# Rectifire_PFC_Solar.net
KiCad netlist of a schematic drawn in Altium Designer
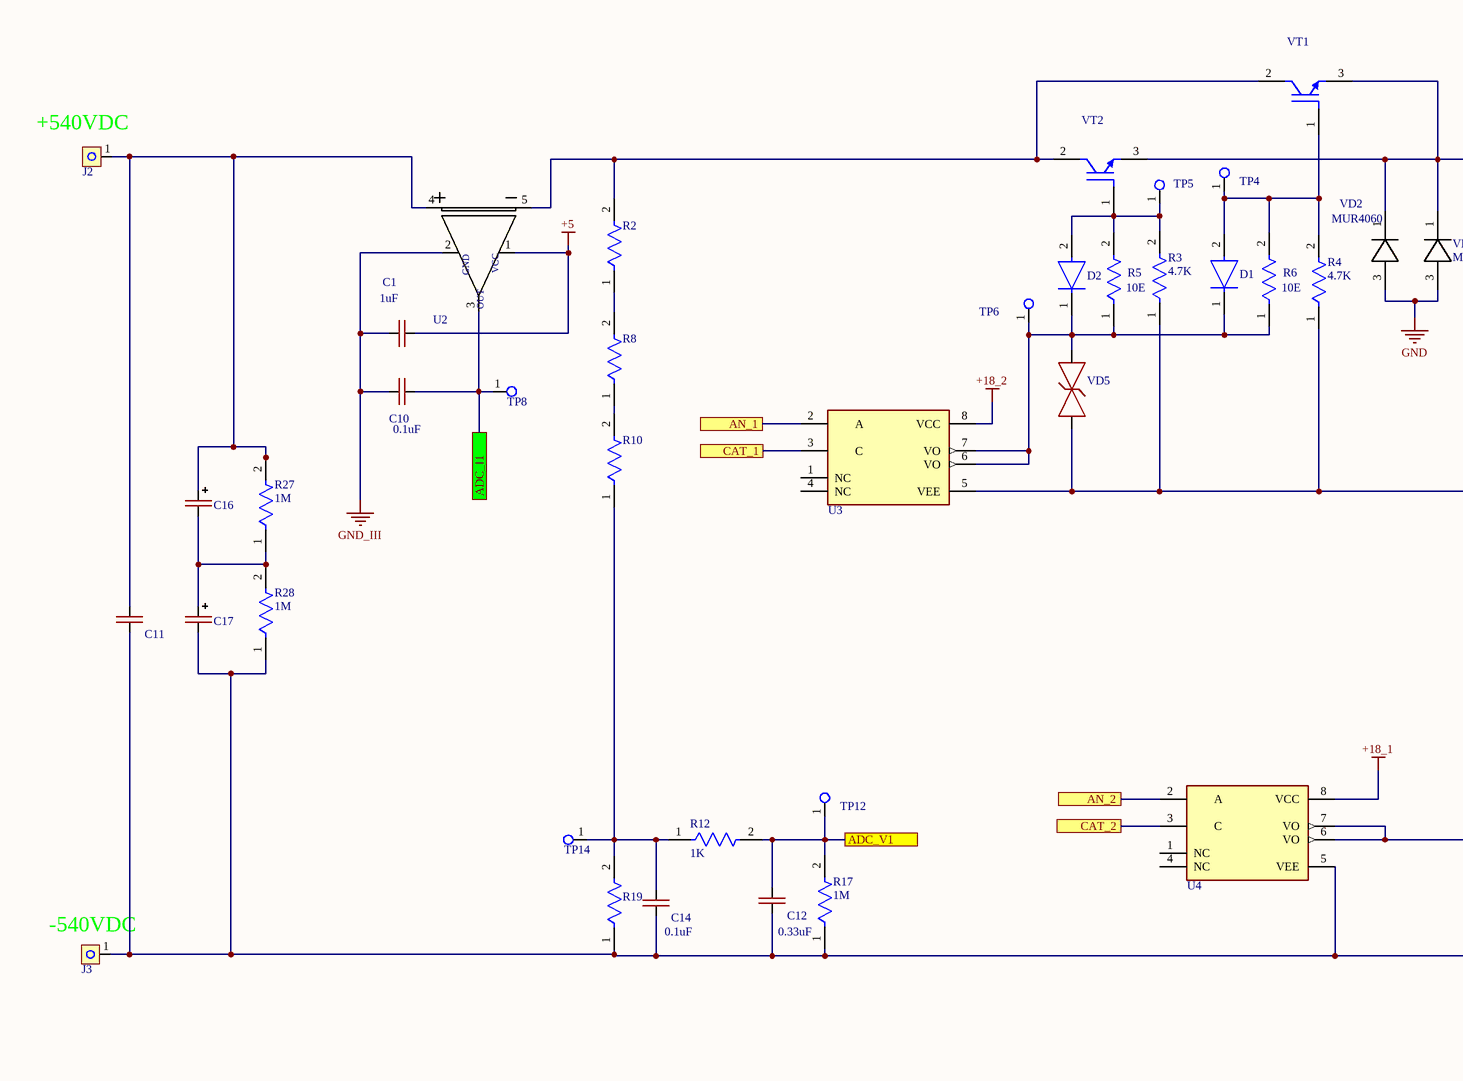
[diagram p0: Rectifire_PFC_Solar.SchDoc, top left]
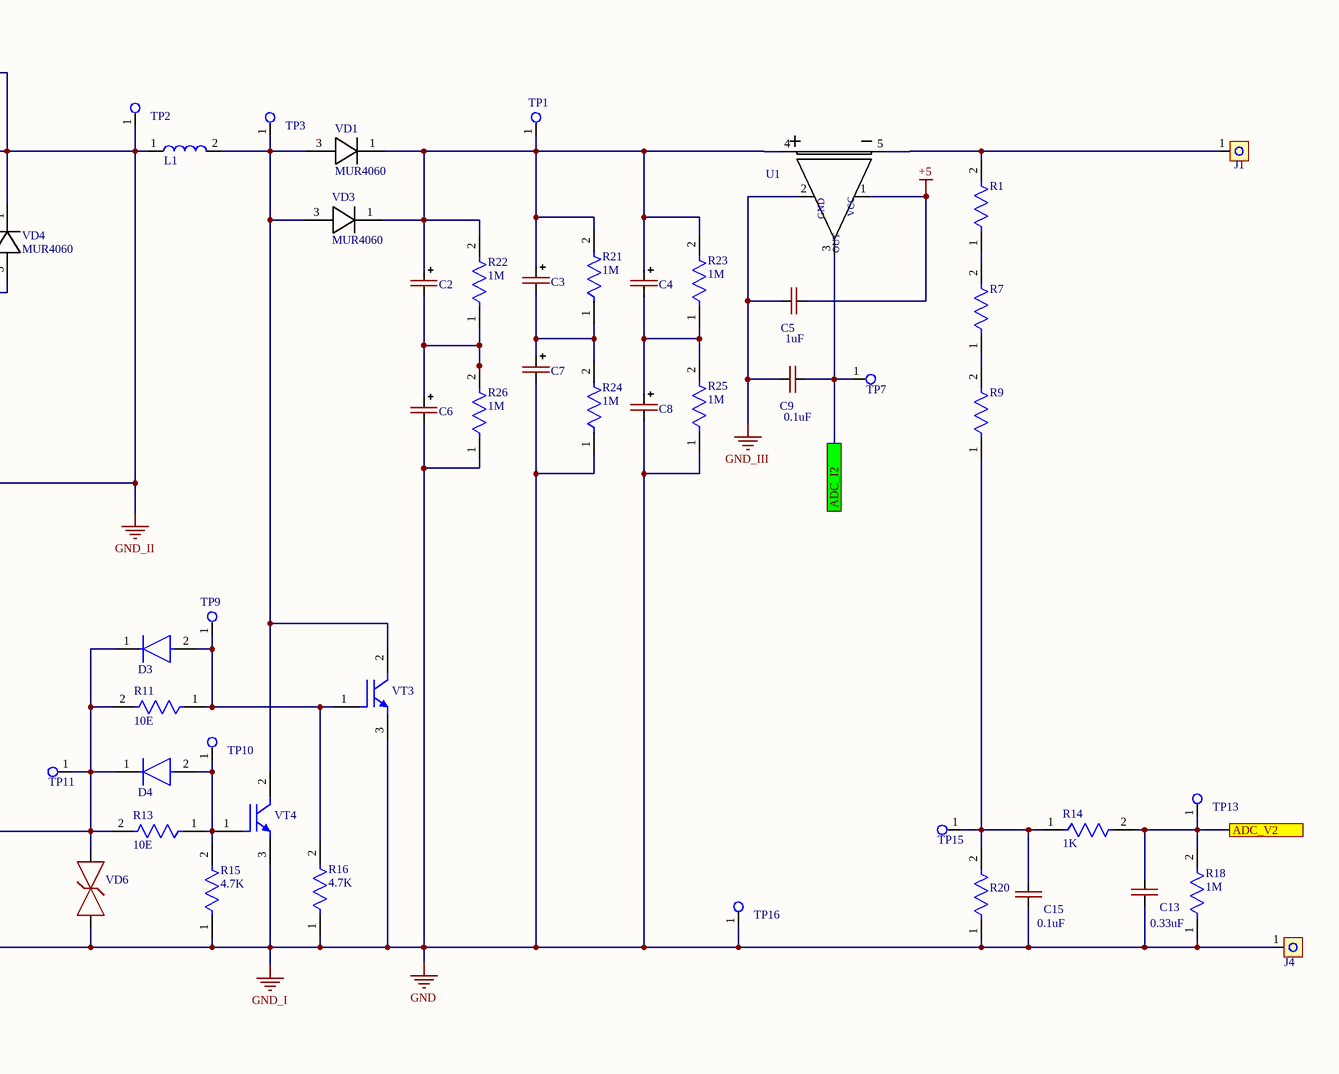
[diagram p1: Rectifire_PFC_Solar.SchDoc, top right]
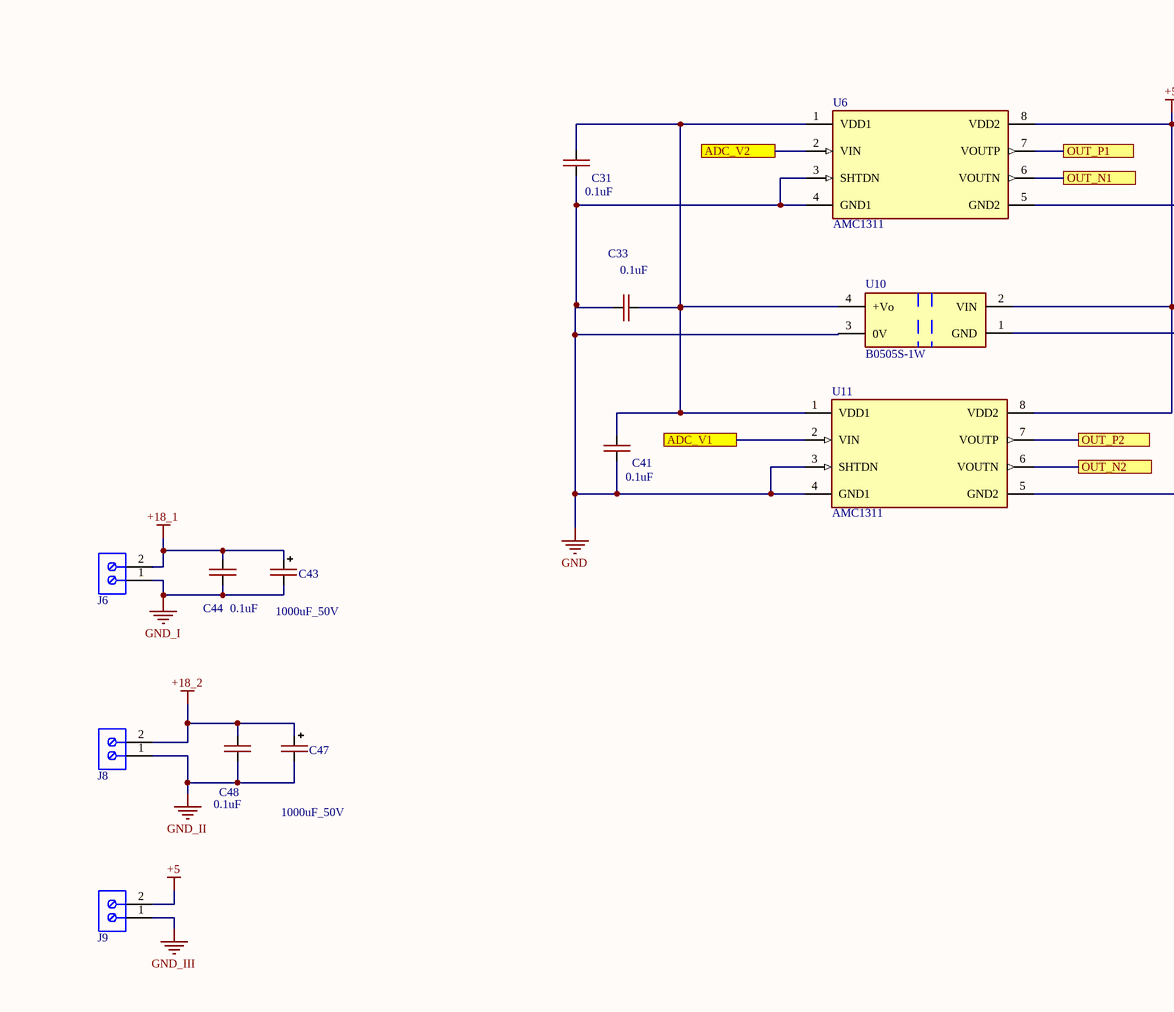
[diagram p2: Rectifire_PFC_Solar.SchDoc, bottom left]
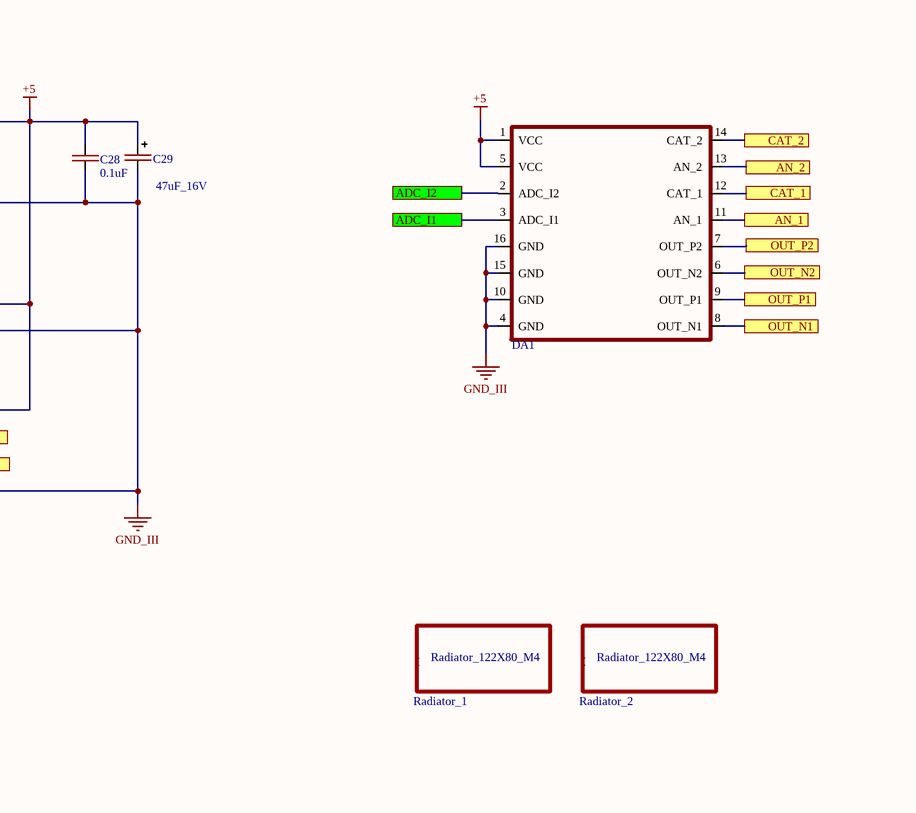
[diagram p3: Rectifire_PFC_Solar.SchDoc, bottom right]

(export (version "E")
  (design (tool "Eeschema 10.0.6"))
  (components
    (comp (ref "C1")
      (value "1uF")
      (footprint "CAP-0805")
      (libsource (lib "PASSIVE_COMPONENTS") (part "CAP-NON-POLAR"))
    )
    (comp (ref "C2")
      (value "CAP-POLAR")
      (footprint "CAP 100uF_500V 22x40mm")
      (libsource (lib "PASSIVE_COMPONENTS") (part "CAP-POLAR"))
    )
    (comp (ref "C3")
      (value "CAP-POLAR")
      (footprint "CAP 100uF_500V 22x40mm")
      (libsource (lib "PASSIVE_COMPONENTS") (part "CAP-POLAR"))
    )
    (comp (ref "C4")
      (value "CAP-POLAR")
      (footprint "CAP 100uF_500V 22x40mm")
      (libsource (lib "PASSIVE_COMPONENTS") (part "CAP-POLAR"))
    )
    (comp (ref "C5")
      (value "1uF")
      (footprint "CAP-0805")
      (libsource (lib "PASSIVE_COMPONENTS") (part "CAP-NON-POLAR"))
    )
    (comp (ref "C6")
      (value "CAP-POLAR")
      (footprint "CAP 100uF_500V 22x40mm")
      (libsource (lib "PASSIVE_COMPONENTS") (part "CAP-POLAR"))
    )
    (comp (ref "C7")
      (value "CAP-POLAR")
      (footprint "CAP 100uF_500V 22x40mm")
      (libsource (lib "PASSIVE_COMPONENTS") (part "CAP-POLAR"))
    )
    (comp (ref "C8")
      (value "CAP-POLAR")
      (footprint "CAP 100uF_500V 22x40mm")
      (libsource (lib "PASSIVE_COMPONENTS") (part "CAP-POLAR"))
    )
    (comp (ref "C9")
      (value "0.1uF")
      (footprint "CAP-0805")
      (libsource (lib "PASSIVE_COMPONENTS") (part "CAP-NON-POLAR"))
    )
    (comp (ref "C10")
      (value "0.1uF")
      (footprint "CAP-0805")
      (libsource (lib "PASSIVE_COMPONENTS") (part "CAP-NON-POLAR"))
    )
    (comp (ref "C11")
      (value "CAP-NON-POLAR")
      (footprint "CAP_4.7uF_630V")
      (libsource (lib "PASSIVE_COMPONENTS") (part "CAP-NON-POLAR"))
    )
    (comp (ref "C12")
      (value "0.33uF")
      (footprint "CAP-0805")
      (libsource (lib "PASSIVE_COMPONENTS") (part "CAP-NON-POLAR"))
    )
    (comp (ref "C13")
      (value "0.33uF")
      (footprint "CAP-0805")
      (libsource (lib "PASSIVE_COMPONENTS") (part "CAP-NON-POLAR"))
    )
    (comp (ref "C14")
      (value "0.1uF")
      (footprint "CAP-0805")
      (libsource (lib "PASSIVE_COMPONENTS") (part "CAP-NON-POLAR"))
    )
    (comp (ref "C15")
      (value "0.1uF")
      (footprint "CAP-0805")
      (libsource (lib "PASSIVE_COMPONENTS") (part "CAP-NON-POLAR"))
    )
    (comp (ref "C16")
      (value "CAP-POLAR")
      (footprint "CAP_POL_36X60")
      (libsource (lib "PASSIVE_COMPONENTS") (part "CAP-POLAR"))
    )
    (comp (ref "C17")
      (value "CAP-POLAR")
      (footprint "CAP_POL_36X60")
      (libsource (lib "PASSIVE_COMPONENTS") (part "CAP-POLAR"))
    )
    (comp (ref "C28")
      (value "0.1uF")
      (footprint "CAP-0805")
      (libsource (lib "PASSIVE_COMPONENTS") (part "CAP-NON-POLAR"))
    )
    (comp (ref "C29")
      (value "47uF_16V")
      (footprint "CAP-TAN-D")
      (libsource (lib "PASSIVE_COMPONENTS") (part "CAP-POLAR"))
    )
    (comp (ref "C31")
      (value "0.1uF")
      (footprint "CAP-0805")
      (libsource (lib "PASSIVE_COMPONENTS") (part "CAP-NON-POLAR"))
    )
    (comp (ref "C33")
      (value "0.1uF")
      (footprint "CAP-0805")
      (libsource (lib "PASSIVE_COMPONENTS") (part "CAP-NON-POLAR"))
    )
    (comp (ref "C41")
      (value "0.1uF")
      (footprint "CAP-0805")
      (libsource (lib "PASSIVE_COMPONENTS") (part "CAP-NON-POLAR"))
    )
    (comp (ref "C43")
      (value "1000uF_50V")
      (footprint "CAPPOL-16x25")
      (libsource (lib "PASSIVE_COMPONENTS") (part "CAP-POLAR"))
    )
    (comp (ref "C44")
      (value "0.1uF")
      (footprint "CAP-0805")
      (libsource (lib "PASSIVE_COMPONENTS") (part "CAP-NON-POLAR"))
    )
    (comp (ref "C47")
      (value "1000uF_50V")
      (footprint "CAPPOL-16x25")
      (libsource (lib "PASSIVE_COMPONENTS") (part "CAP-POLAR"))
    )
    (comp (ref "C48")
      (value "0.1uF")
      (footprint "CAP-0805")
      (libsource (lib "PASSIVE_COMPONENTS") (part "CAP-NON-POLAR"))
    )
    (comp (ref "D1") (value "US1G") (footprint "DO-214AA") (libsource (lib "Diodes") (part "US1G")))
    (comp (ref "D2") (value "US1G") (footprint "DO-214AA") (libsource (lib "Diodes") (part "US1G")))
    (comp (ref "D3") (value "US1G") (footprint "DO-214AA") (libsource (lib "Diodes") (part "US1G")))
    (comp (ref "D4") (value "US1G") (footprint "DO-214AA") (libsource (lib "Diodes") (part "US1G")))
    (comp (ref "DA1")
      (value "BOARD_PFC")
      (footprint "BOARD_PFC")
      (libsource (lib "BOARD_PFC") (part "BOARD_PFC"))
    )
    (comp (ref "J1")
      (value "MG_136_HT")
      (footprint "Conn_MEIGAN_MG136HT")
      (libsource (lib "") (part "Connector_MEIGAN_MG136HT_1"))
    )
    (comp (ref "J2")
      (value "MG_136_HT")
      (footprint "Conn_MEIGAN_MG136HT")
      (libsource (lib "Connectors") (part "Connector_MEIGAN_MG136HT"))
    )
    (comp (ref "J3")
      (value "MG_136_HT")
      (footprint "Conn_MEIGAN_MG136HT")
      (libsource (lib "Connectors") (part "Connector_MEIGAN_MG136HT"))
    )
    (comp (ref "J4")
      (value "MG_136_HT")
      (footprint "Conn_MEIGAN_MG136HT")
      (libsource (lib "") (part "Connector_MEIGAN_MG136HT_1"))
    )
    (comp (ref "J6")
      (value "691102710002")
      (footprint "691102710002")
      (description "WR-TBL Series 102 Horizontal Entry Modular, THT, pitch 5mm, 2p")
      (fields (field (name "MANUFACTURER") "Wurth Elektronik"))
      (libsource (lib "Altium_WR-TBL (rev23f)") (part "691102710002"))
    )
    (comp (ref "J8")
      (value "691102710002")
      (footprint "691102710002")
      (description "WR-TBL Series 102 Horizontal Entry Modular, THT, pitch 5mm, 2p")
      (fields (field (name "MANUFACTURER") "Wurth Elektronik"))
      (libsource (lib "Altium_WR-TBL (rev23f)") (part "691102710002"))
    )
    (comp (ref "J9")
      (value "691102710002")
      (footprint "691102710002")
      (description "WR-TBL Series 102 Horizontal Entry Modular, THT, pitch 5mm, 2p")
      (fields (field (name "MANUFACTURER") "Wurth Elektronik"))
      (libsource (lib "Altium_WR-TBL (rev23f)") (part "691102710002"))
    )
    (comp (ref "L1") (value "Coil") (footprint "30A_10uH") (libsource (lib "Transformers") (part "Coil")))
    (comp (ref "R1")
      (value "~")
      (footprint "RES-2512")
      (libsource (lib "PASSIVE_COMPONENTS") (part "RES-CONST"))
    )
    (comp (ref "R2")
      (value "~")
      (footprint "RES-2512")
      (libsource (lib "PASSIVE_COMPONENTS") (part "RES-CONST"))
    )
    (comp (ref "R3")
      (value "4.7K")
      (footprint "RES-0805")
      (libsource (lib "PASSIVE_COMPONENTS") (part "RES-CONST"))
    )
    (comp (ref "R4")
      (value "4.7K")
      (footprint "RES-0805")
      (libsource (lib "PASSIVE_COMPONENTS") (part "RES-CONST"))
    )
    (comp (ref "R5")
      (value "10E")
      (footprint "RES_SMD_1210_IPC_A")
      (libsource (lib "PASSIVE_COMPONENTS") (part "RES_1210"))
    )
    (comp (ref "R6")
      (value "10E")
      (footprint "RES_SMD_1210_IPC_A")
      (libsource (lib "PASSIVE_COMPONENTS") (part "RES_1210"))
    )
    (comp (ref "R7")
      (value "~")
      (footprint "RES-2512")
      (libsource (lib "PASSIVE_COMPONENTS") (part "RES-CONST"))
    )
    (comp (ref "R8")
      (value "~")
      (footprint "RES-2512")
      (libsource (lib "PASSIVE_COMPONENTS") (part "RES-CONST"))
    )
    (comp (ref "R9")
      (value "~")
      (footprint "RES-2512")
      (libsource (lib "PASSIVE_COMPONENTS") (part "RES-CONST"))
    )
    (comp (ref "R10")
      (value "~")
      (footprint "RES-2512")
      (libsource (lib "PASSIVE_COMPONENTS") (part "RES-CONST"))
    )
    (comp (ref "R11")
      (value "10E")
      (footprint "RES_SMD_1210_IPC_A")
      (libsource (lib "PASSIVE_COMPONENTS") (part "RES_1210"))
    )
    (comp (ref "R12")
      (value "1K")
      (footprint "RES-0805")
      (libsource (lib "PASSIVE_COMPONENTS") (part "RES-CONST"))
    )
    (comp (ref "R13")
      (value "10E")
      (footprint "RES_SMD_1210_IPC_A")
      (libsource (lib "PASSIVE_COMPONENTS") (part "RES_1210"))
    )
    (comp (ref "R14")
      (value "1K")
      (footprint "RES-0805")
      (libsource (lib "PASSIVE_COMPONENTS") (part "RES-CONST"))
    )
    (comp (ref "R15")
      (value "4.7K")
      (footprint "RES-0805")
      (libsource (lib "PASSIVE_COMPONENTS") (part "RES-CONST"))
    )
    (comp (ref "R16")
      (value "4.7K")
      (footprint "RES-0805")
      (libsource (lib "PASSIVE_COMPONENTS") (part "RES-CONST"))
    )
    (comp (ref "R17")
      (value "1M")
      (footprint "RES-0805")
      (libsource (lib "PASSIVE_COMPONENTS") (part "RES-CONST"))
    )
    (comp (ref "R18")
      (value "1M")
      (footprint "RES-0805")
      (libsource (lib "PASSIVE_COMPONENTS") (part "RES-CONST"))
    )
    (comp (ref "R19")
      (value "RES_1210")
      (footprint "RES_SMD_1210_IPC_B")
      (libsource (lib "PASSIVE_COMPONENTS") (part "RES_1210"))
    )
    (comp (ref "R20")
      (value "RES_1210")
      (footprint "RES_SMD_1210_IPC_B")
      (libsource (lib "PASSIVE_COMPONENTS") (part "RES_1210"))
    )
    (comp (ref "R21")
      (value "1M")
      (footprint "RES-2512")
      (description "4.7K")
      (libsource (lib "PASSIVE_COMPONENTS") (part "RES-CONST"))
    )
    (comp (ref "R22")
      (value "1M")
      (footprint "RES-2512")
      (description "4.7K")
      (libsource (lib "PASSIVE_COMPONENTS") (part "RES-CONST"))
    )
    (comp (ref "R23")
      (value "1M")
      (footprint "RES-2512")
      (description "4.7K")
      (libsource (lib "PASSIVE_COMPONENTS") (part "RES-CONST"))
    )
    (comp (ref "R24")
      (value "1M")
      (footprint "RES-2512")
      (description "4.7K")
      (libsource (lib "PASSIVE_COMPONENTS") (part "RES-CONST"))
    )
    (comp (ref "R25")
      (value "1M")
      (footprint "RES-2512")
      (description "4.7K")
      (libsource (lib "PASSIVE_COMPONENTS") (part "RES-CONST"))
    )
    (comp (ref "R26")
      (value "1M")
      (footprint "RES-2512")
      (description "4.7K")
      (libsource (lib "PASSIVE_COMPONENTS") (part "RES-CONST"))
    )
    (comp (ref "R27")
      (value "1M")
      (footprint "RES-2512")
      (description "4.7K")
      (libsource (lib "PASSIVE_COMPONENTS") (part "RES-CONST"))
    )
    (comp (ref "R28")
      (value "1M")
      (footprint "RES-2512")
      (description "4.7K")
      (libsource (lib "PASSIVE_COMPONENTS") (part "RES-CONST"))
    )
    (comp (ref "Radiator_1")
      (value "Radiator_122X80_M4")
      (footprint "Radiator_122X80_M4")
      (libsource (lib "Radiator_122X80_M4") (part "Radiator_122X80_M4"))
    )
    (comp (ref "Radiator_2")
      (value "Radiator_122X80_M4")
      (footprint "Radiator_122X80_M4")
      (libsource (lib "Radiator_122X80_M4") (part "Radiator_122X80_M4"))
    )
    (comp (ref "TP1")
      (value "Test_Point_PCB")
      (footprint "Test_Point")
      (description "Test_Point")
      (libsource (lib "Connectors") (part "TP_PCB?"))
    )
    (comp (ref "TP2")
      (value "Test_Point_PCB")
      (footprint "Test_Point")
      (description "Test_Point")
      (libsource (lib "Connectors") (part "TP_PCB?"))
    )
    (comp (ref "TP3")
      (value "Test_Point_PCB")
      (footprint "Test_Point")
      (description "Test_Point")
      (libsource (lib "Connectors") (part "TP_PCB?"))
    )
    (comp (ref "TP4")
      (value "Test_Point_PCB")
      (footprint "Test_Point")
      (description "Test_Point")
      (libsource (lib "Connectors") (part "TP_PCB?"))
    )
    (comp (ref "TP5")
      (value "Test_Point_PCB")
      (footprint "Test_Point")
      (description "Test_Point")
      (libsource (lib "Connectors") (part "TP_PCB?"))
    )
    (comp (ref "TP6")
      (value "Test_Point_PCB")
      (footprint "Test_Point")
      (description "Test_Point")
      (libsource (lib "Connectors") (part "TP_PCB?"))
    )
    (comp (ref "TP7")
      (value "Test_Point_PCB")
      (footprint "Test_Point")
      (description "Test_Point")
      (libsource (lib "Connectors") (part "TP_PCB?"))
    )
    (comp (ref "TP8")
      (value "Test_Point_PCB")
      (footprint "Test_Point")
      (description "Test_Point")
      (libsource (lib "Connectors") (part "TP_PCB?"))
    )
    (comp (ref "TP9")
      (value "Test_Point_PCB")
      (footprint "Test_Point")
      (description "Test_Point")
      (libsource (lib "Connectors") (part "TP_PCB?"))
    )
    (comp (ref "TP10")
      (value "Test_Point_PCB")
      (footprint "Test_Point")
      (description "Test_Point")
      (libsource (lib "Connectors") (part "TP_PCB?"))
    )
    (comp (ref "TP11")
      (value "Test_Point_PCB")
      (footprint "Test_Point")
      (description "Test_Point")
      (libsource (lib "Connectors") (part "TP_PCB?"))
    )
    (comp (ref "TP12")
      (value "Test_Point_PCB")
      (footprint "Test_Point")
      (description "Test_Point")
      (libsource (lib "Connectors") (part "TP_PCB?"))
    )
    (comp (ref "TP13")
      (value "Test_Point_PCB")
      (footprint "Test_Point")
      (description "Test_Point")
      (libsource (lib "Connectors") (part "TP_PCB?"))
    )
    (comp (ref "TP14")
      (value "Test_Point_PCB")
      (footprint "Test_Point")
      (description "Test_Point")
      (libsource (lib "Connectors") (part "TP_PCB?"))
    )
    (comp (ref "TP15")
      (value "Test_Point_PCB")
      (footprint "Test_Point")
      (description "Test_Point")
      (libsource (lib "Connectors") (part "TP_PCB?"))
    )
    (comp (ref "TP16")
      (value "Test_Point_PCB")
      (footprint "Test_Point")
      (description "Test_Point")
      (libsource (lib "Connectors") (part "TP_PCB?"))
    )
    (comp (ref "U1")
      (value "ACS758")
      (footprint "ACS758-100")
      (libsource (lib "Integrated_Circuts") (part "ACS758"))
    )
    (comp (ref "U2")
      (value "ACS758")
      (footprint "ACS758-100")
      (libsource (lib "Integrated_Circuts") (part "ACS758"))
    )
    (comp (ref "U3")
      (value "HCPL-3120")
      (footprint "HCPL-3120")
      (libsource (lib "Integrated_Circuts") (part "HCPL-3120"))
    )
    (comp (ref "U4")
      (value "HCPL-3120")
      (footprint "HCPL-3120")
      (libsource (lib "Integrated_Circuts") (part "HCPL-3120"))
    )
    (comp (ref "U6")
      (value "AMC1311")
      (footprint "FP-DWV0008A-MFG")
      (libsource (lib "Integrated_Circuts") (part "AMC1311"))
    )
    (comp (ref "U10")
      (value "B0505S-1W")
      (footprint "B0505S-1W")
      (libsource (lib "Integrated_Circuts") (part "B0505S-1W"))
    )
    (comp (ref "U11")
      (value "AMC1311")
      (footprint "FP-DWV0008A-MFG")
      (libsource (lib "Integrated_Circuts") (part "AMC1311"))
    )
    (comp (ref "VD1") (value "MUR4060") (footprint "TO-247-2") (libsource (lib "Diodes") (part "MUR4060")))
    (comp (ref "VD2") (value "MUR4060") (footprint "TO-247-2") (libsource (lib "Diodes") (part "MUR4060")))
    (comp (ref "VD3") (value "MUR4060") (footprint "TO-247-2") (libsource (lib "Diodes") (part "MUR4060")))
    (comp (ref "VD4") (value "MUR4060") (footprint "TO-247-2") (libsource (lib "Diodes") (part "MUR4060")))
    (comp (ref "VD5")
      (value "Suppressor")
      (footprint "DO-214AA")
      (libsource (lib "Diodes") (part "Suppressor"))
    )
    (comp (ref "VD6")
      (value "Suppressor")
      (footprint "DO-214AA")
      (libsource (lib "Diodes") (part "Suppressor"))
    )
    (comp (ref "VT1")
      (value "IGBT 60N120T")
      (footprint "TO-264-3")
      (description "IGBT 60N120T TO-264-3")
      (libsource (lib "Transistors") (part "IGBT 60N120T"))
    )
    (comp (ref "VT2")
      (value "IGBT 60N120T")
      (footprint "TO-264-3")
      (description "IGBT 60N120T TO-264-3")
      (libsource (lib "Transistors") (part "IGBT 60N120T"))
    )
    (comp (ref "VT3")
      (value "IGBT 60N120T")
      (footprint "TO-264-3")
      (description "IGBT 60N120T TO-264-3")
      (libsource (lib "Transistors") (part "IGBT 60N120T"))
    )
    (comp (ref "VT4")
      (value "IGBT 60N120T")
      (footprint "TO-264-3")
      (description "IGBT 60N120T TO-264-3")
      (libsource (lib "Transistors") (part "IGBT 60N120T"))
    )
  )
  (nets
    (net (code "1") (name "+5") (class "Default")
      (node (ref "C1") (pin "2") (pinfunction "2_2") (pintype "passive"))
      (node (ref "C28") (pin "1") (pinfunction "1_1") (pintype "passive"))
      (node (ref "C29") (pin "1") (pinfunction "+_1") (pintype "passive"))
      (node (ref "C5") (pin "2") (pinfunction "2_2") (pintype "passive"))
      (node (ref "DA1") (pin "1") (pinfunction "VCC_1") (pintype "passive"))
      (node (ref "DA1") (pin "5") (pinfunction "VCC_5") (pintype "passive"))
      (node (ref "J9") (pin "2") (pinfunction "2_2") (pintype "passive"))
      (node (ref "U1") (pin "1") (pinfunction "+VCC_1") (pintype "passive"))
      (node (ref "U10") (pin "2") (pinfunction "VIN_2") (pintype "power_in"))
      (node (ref "U11") (pin "8") (pinfunction "VDD2_8") (pintype "power_in"))
      (node (ref "U2") (pin "1") (pinfunction "+VCC_1") (pintype "passive"))
      (node (ref "U6") (pin "8") (pinfunction "VDD2_8") (pintype "power_in"))
    )
    (net (code "2") (name "+18_1") (class "Default")
      (node (ref "C43") (pin "1") (pinfunction "+_1") (pintype "passive"))
      (node (ref "C44") (pin "2") (pinfunction "2_2") (pintype "passive"))
      (node (ref "J6") (pin "2") (pinfunction "2_2") (pintype "passive"))
      (node (ref "U4") (pin "8") (pinfunction "VCC_8") (pintype "power_in"))
    )
    (net (code "3") (name "+18_2") (class "Default")
      (node (ref "C47") (pin "1") (pinfunction "+_1") (pintype "passive"))
      (node (ref "C48") (pin "2") (pinfunction "2_2") (pintype "passive"))
      (node (ref "J8") (pin "2") (pinfunction "2_2") (pintype "passive"))
      (node (ref "U3") (pin "8") (pinfunction "VCC_8") (pintype "power_in"))
    )
    (net (code "4") (name "/ADC_I1") (class "Default")
      (node (ref "C10") (pin "2") (pinfunction "2_2") (pintype "passive"))
      (node (ref "DA1") (pin "3") (pinfunction "ADC_I1_3") (pintype "passive"))
      (node (ref "TP8") (pin "1") (pinfunction "G9_1") (pintype "passive"))
      (node (ref "U2") (pin "3") (pinfunction "OUT_3") (pintype "passive"))
    )
    (net (code "5") (name "/ADC_I2") (class "Default")
      (node (ref "C9") (pin "2") (pinfunction "2_2") (pintype "passive"))
      (node (ref "DA1") (pin "2") (pinfunction "ADC_I2_2") (pintype "passive"))
      (node (ref "TP7") (pin "1") (pinfunction "G9_1") (pintype "passive"))
      (node (ref "U1") (pin "3") (pinfunction "OUT_3") (pintype "passive"))
    )
    (net (code "6") (name "/ADC_V1") (class "Default")
      (node (ref "C12") (pin "2") (pinfunction "2_2") (pintype "passive"))
      (node (ref "R12") (pin "2") (pinfunction "2_2") (pintype "passive"))
      (node (ref "R17") (pin "2") (pinfunction "2_2") (pintype "passive"))
      (node (ref "TP12") (pin "1") (pinfunction "G9_1") (pintype "passive"))
      (node (ref "U11") (pin "2") (pinfunction "VIN_2") (pintype "input"))
    )
    (net (code "7") (name "/ADC_V2") (class "Default")
      (node (ref "C13") (pin "2") (pinfunction "2_2") (pintype "passive"))
      (node (ref "R14") (pin "2") (pinfunction "2_2") (pintype "passive"))
      (node (ref "R18") (pin "2") (pinfunction "2_2") (pintype "passive"))
      (node (ref "TP13") (pin "1") (pinfunction "G9_1") (pintype "passive"))
      (node (ref "U6") (pin "2") (pinfunction "VIN_2") (pintype "input"))
    )
    (net (code "8") (name "/AN_1") (class "Default")
      (node (ref "DA1") (pin "11") (pinfunction "AN_1_11") (pintype "passive"))
      (node (ref "U3") (pin "2") (pinfunction "A_2") (pintype "passive"))
    )
    (net (code "9") (name "/AN_2") (class "Default")
      (node (ref "DA1") (pin "13") (pinfunction "AN_2_13") (pintype "passive"))
      (node (ref "U4") (pin "2") (pinfunction "A_2") (pintype "passive"))
    )
    (net (code "10") (name "/CAT_1") (class "Default")
      (node (ref "DA1") (pin "12") (pinfunction "CAT_1_12") (pintype "passive"))
      (node (ref "U3") (pin "3") (pinfunction "C_3") (pintype "passive"))
    )
    (net (code "11") (name "/CAT_2") (class "Default")
      (node (ref "DA1") (pin "14") (pinfunction "CAT_2_14") (pintype "passive"))
      (node (ref "U4") (pin "3") (pinfunction "C_3") (pintype "passive"))
    )
    (net (code "12") (name "/OUT_N1") (class "Default")
      (node (ref "DA1") (pin "8") (pinfunction "OUT_N1_8") (pintype "passive"))
      (node (ref "U6") (pin "6") (pinfunction "VOUTN_6") (pintype "output"))
    )
    (net (code "13") (name "/OUT_N2") (class "Default")
      (node (ref "DA1") (pin "6") (pinfunction "OUT_N2_6") (pintype "passive"))
      (node (ref "U11") (pin "6") (pinfunction "VOUTN_6") (pintype "output"))
    )
    (net (code "14") (name "/OUT_P1") (class "Default")
      (node (ref "DA1") (pin "9") (pinfunction "OUT_P1_9") (pintype "passive"))
      (node (ref "U6") (pin "7") (pinfunction "VOUTP_7") (pintype "output"))
    )
    (net (code "15") (name "/OUT_P2") (class "Default")
      (node (ref "DA1") (pin "7") (pinfunction "OUT_P2_7") (pintype "passive"))
      (node (ref "U11") (pin "7") (pinfunction "VOUTP_7") (pintype "output"))
    )
    (net (code "16") (name "GND") (class "Default")
      (node (ref "C11") (pin "1") (pinfunction "1_1") (pintype "passive"))
      (node (ref "C12") (pin "1") (pinfunction "1_1") (pintype "passive"))
      (node (ref "C13") (pin "1") (pinfunction "1_1") (pintype "passive"))
      (node (ref "C14") (pin "1") (pinfunction "1_1") (pintype "passive"))
      (node (ref "C15") (pin "1") (pinfunction "1_1") (pintype "passive"))
      (node (ref "C17") (pin "2") (pinfunction "-_2") (pintype "passive"))
      (node (ref "C31") (pin "1") (pinfunction "1_1") (pintype "passive"))
      (node (ref "C33") (pin "2") (pinfunction "2_2") (pintype "passive"))
      (node (ref "C41") (pin "1") (pinfunction "1_1") (pintype "passive"))
      (node (ref "C43") (pin "2") (pinfunction "-_2") (pintype "passive"))
      (node (ref "C44") (pin "1") (pinfunction "1_1") (pintype "passive"))
      (node (ref "C6") (pin "2") (pinfunction "-_2") (pintype "passive"))
      (node (ref "C7") (pin "2") (pinfunction "-_2") (pintype "passive"))
      (node (ref "C8") (pin "2") (pinfunction "-_2") (pintype "passive"))
      (node (ref "J3") (pin "1") (pinfunction "17_1") (pintype "passive"))
      (node (ref "J4") (pin "1") (pinfunction "17_1") (pintype "passive"))
      (node (ref "J6") (pin "1") (pinfunction "1_1") (pintype "passive"))
      (node (ref "R15") (pin "1") (pinfunction "1_1") (pintype "passive"))
      (node (ref "R16") (pin "1") (pinfunction "1_1") (pintype "passive"))
      (node (ref "R17") (pin "1") (pinfunction "1_1") (pintype "passive"))
      (node (ref "R18") (pin "1") (pinfunction "1_1") (pintype "passive"))
      (node (ref "R19") (pin "1") (pinfunction "1_1") (pintype "passive"))
      (node (ref "R20") (pin "1") (pinfunction "1_1") (pintype "passive"))
      (node (ref "R24") (pin "1") (pinfunction "1_1") (pintype "passive"))
      (node (ref "R25") (pin "1") (pinfunction "1_1") (pintype "passive"))
      (node (ref "R26") (pin "1") (pinfunction "1_1") (pintype "passive"))
      (node (ref "R28") (pin "1") (pinfunction "1_1") (pintype "passive"))
      (node (ref "TP16") (pin "1") (pinfunction "G9_1") (pintype "passive"))
      (node (ref "U10") (pin "3") (pinfunction "0V_3") (pintype "power_in"))
      (node (ref "U11") (pin "3") (pinfunction "SHTDN_3") (pintype "input"))
      (node (ref "U11") (pin "4") (pinfunction "GND1_4") (pintype "power_in"))
      (node (ref "U4") (pin "5") (pinfunction "VEE_5") (pintype "power_in"))
      (node (ref "U6") (pin "3") (pinfunction "SHTDN_3") (pintype "input"))
      (node (ref "U6") (pin "4") (pinfunction "GND1_4") (pintype "power_in"))
      (node (ref "VD2") (pin "3") (pinfunction "3_3") (pintype "passive"))
      (node (ref "VD4") (pin "3") (pinfunction "3_3") (pintype "passive"))
      (node (ref "VD6") (pin "1") (pinfunction "C_1") (pintype "passive"))
      (node (ref "VT3") (pin "3") (pinfunction "E_3") (pintype "passive"))
      (node (ref "VT4") (pin "3") (pinfunction "E_3") (pintype "passive"))
    )
    (net (code "17") (name "GND_II") (class "Default")
      (node (ref "C47") (pin "2") (pinfunction "-_2") (pintype "passive"))
      (node (ref "C48") (pin "1") (pinfunction "1_1") (pintype "passive"))
      (node (ref "J8") (pin "1") (pinfunction "1_1") (pintype "passive"))
      (node (ref "L1") (pin "1") (pinfunction "1_1") (pintype "passive"))
      (node (ref "R3") (pin "1") (pinfunction "1_1") (pintype "passive"))
      (node (ref "R4") (pin "1") (pinfunction "1_1") (pintype "passive"))
      (node (ref "TP2") (pin "1") (pinfunction "G9_1") (pintype "passive"))
      (node (ref "U3") (pin "5") (pinfunction "VEE_5") (pintype "power_in"))
      (node (ref "VD2") (pin "1") (pinfunction "1_1") (pintype "passive"))
      (node (ref "VD4") (pin "1") (pinfunction "1_1") (pintype "passive"))
      (node (ref "VD5") (pin "1") (pinfunction "C_1") (pintype "passive"))
      (node (ref "VT1") (pin "3") (pinfunction "E_3") (pintype "passive"))
      (node (ref "VT2") (pin "3") (pinfunction "E_3") (pintype "passive"))
    )
    (net (code "18") (name "GND_III") (class "Default")
      (node (ref "C1") (pin "1") (pinfunction "1_1") (pintype "passive"))
      (node (ref "C10") (pin "1") (pinfunction "1_1") (pintype "passive"))
      (node (ref "C28") (pin "2") (pinfunction "2_2") (pintype "passive"))
      (node (ref "C29") (pin "2") (pinfunction "-_2") (pintype "passive"))
      (node (ref "C5") (pin "1") (pinfunction "1_1") (pintype "passive"))
      (node (ref "C9") (pin "1") (pinfunction "1_1") (pintype "passive"))
      (node (ref "DA1") (pin "10") (pinfunction "GND_10") (pintype "passive"))
      (node (ref "DA1") (pin "15") (pinfunction "GND_15") (pintype "passive"))
      (node (ref "DA1") (pin "16") (pinfunction "GND_16") (pintype "passive"))
      (node (ref "DA1") (pin "4") (pinfunction "GND_4") (pintype "passive"))
      (node (ref "J9") (pin "1") (pinfunction "1_1") (pintype "passive"))
      (node (ref "U1") (pin "2") (pinfunction "GND_2") (pintype "passive"))
      (node (ref "U10") (pin "1") (pinfunction "GND_1") (pintype "power_in"))
      (node (ref "U11") (pin "5") (pinfunction "GND2_5") (pintype "power_in"))
      (node (ref "U2") (pin "2") (pinfunction "GND_2") (pintype "passive"))
      (node (ref "U6") (pin "5") (pinfunction "GND2_5") (pintype "power_in"))
    )
    (net (code "19") (name "Net-(C2-+)") (class "Default")
      (node (ref "C2") (pin "1") (pinfunction "+_1") (pintype "passive"))
      (node (ref "C3") (pin "1") (pinfunction "+_1") (pintype "passive"))
      (node (ref "C4") (pin "1") (pinfunction "+_1") (pintype "passive"))
      (node (ref "R21") (pin "2") (pinfunction "2_2") (pintype "passive"))
      (node (ref "R22") (pin "2") (pinfunction "2_2") (pintype "passive"))
      (node (ref "R23") (pin "2") (pinfunction "2_2") (pintype "passive"))
      (node (ref "TP1") (pin "1") (pinfunction "G9_1") (pintype "passive"))
      (node (ref "U1") (pin "4") (pinfunction "+IP_4") (pintype "passive"))
      (node (ref "VD1") (pin "1") (pinfunction "1_1") (pintype "passive"))
      (node (ref "VD3") (pin "1") (pinfunction "1_1") (pintype "passive"))
    )
    (net (code "20") (name "Net-(C2--)") (class "Default")
      (node (ref "C2") (pin "2") (pinfunction "-_2") (pintype "passive"))
      (node (ref "C6") (pin "1") (pinfunction "+_1") (pintype "passive"))
      (node (ref "R22") (pin "1") (pinfunction "1_1") (pintype "passive"))
      (node (ref "R26") (pin "2") (pinfunction "2_2") (pintype "passive"))
    )
    (net (code "21") (name "Net-(C3--)") (class "Default")
      (node (ref "C3") (pin "2") (pinfunction "-_2") (pintype "passive"))
      (node (ref "C7") (pin "1") (pinfunction "+_1") (pintype "passive"))
      (node (ref "R21") (pin "1") (pinfunction "1_1") (pintype "passive"))
      (node (ref "R24") (pin "2") (pinfunction "2_2") (pintype "passive"))
    )
    (net (code "22") (name "Net-(C4--)") (class "Default")
      (node (ref "C4") (pin "2") (pinfunction "-_2") (pintype "passive"))
      (node (ref "C8") (pin "1") (pinfunction "+_1") (pintype "passive"))
      (node (ref "R23") (pin "1") (pinfunction "1_1") (pintype "passive"))
      (node (ref "R25") (pin "2") (pinfunction "2_2") (pintype "passive"))
    )
    (net (code "23") (name "Net-(C16-+)") (class "Default")
      (node (ref "C11") (pin "2") (pinfunction "2_2") (pintype "passive"))
      (node (ref "C16") (pin "1") (pinfunction "+_1") (pintype "passive"))
      (node (ref "J2") (pin "1") (pinfunction "17_1") (pintype "passive"))
      (node (ref "R27") (pin "2") (pinfunction "2_2") (pintype "passive"))
      (node (ref "U2") (pin "4") (pinfunction "+IP_4") (pintype "passive"))
    )
    (net (code "24") (name "Net-(C16--)") (class "Default")
      (node (ref "C16") (pin "2") (pinfunction "-_2") (pintype "passive"))
      (node (ref "C17") (pin "1") (pinfunction "+_1") (pintype "passive"))
      (node (ref "R27") (pin "1") (pinfunction "1_1") (pintype "passive"))
      (node (ref "R28") (pin "2") (pinfunction "2_2") (pintype "passive"))
    )
    (net (code "25") (name "Net-(D1-A)") (class "Default")
      (node (ref "D1") (pin "2") (pinfunction "A_2") (pintype "passive"))
      (node (ref "R4") (pin "2") (pinfunction "2_2") (pintype "passive"))
      (node (ref "R6") (pin "2") (pinfunction "2_2") (pintype "passive"))
      (node (ref "TP4") (pin "1") (pinfunction "G9_1") (pintype "passive"))
      (node (ref "VT1") (pin "1") (pinfunction "G_1") (pintype "passive"))
    )
    (net (code "26") (name "Net-(D1-C)") (class "Default")
      (node (ref "D1") (pin "1") (pinfunction "C_1") (pintype "passive"))
      (node (ref "D2") (pin "1") (pinfunction "C_1") (pintype "passive"))
      (node (ref "R5") (pin "1") (pinfunction "1_1") (pintype "passive"))
      (node (ref "R6") (pin "1") (pinfunction "1_1") (pintype "passive"))
      (node (ref "TP6") (pin "1") (pinfunction "G9_1") (pintype "passive"))
      (node (ref "U3") (pin "6") (pinfunction "VO_6") (pintype "output"))
      (node (ref "U3") (pin "7") (pinfunction "VO_7") (pintype "output"))
      (node (ref "VD5") (pin "2") (pinfunction "A_2") (pintype "passive"))
    )
    (net (code "27") (name "Net-(D2-A)") (class "Default")
      (node (ref "D2") (pin "2") (pinfunction "A_2") (pintype "passive"))
      (node (ref "R3") (pin "2") (pinfunction "2_2") (pintype "passive"))
      (node (ref "R5") (pin "2") (pinfunction "2_2") (pintype "passive"))
      (node (ref "TP5") (pin "1") (pinfunction "G9_1") (pintype "passive"))
      (node (ref "VT2") (pin "1") (pinfunction "G_1") (pintype "passive"))
    )
    (net (code "28") (name "Net-(D3-A)") (class "Default")
      (node (ref "D3") (pin "2") (pinfunction "A_2") (pintype "passive"))
      (node (ref "R11") (pin "1") (pinfunction "1_1") (pintype "passive"))
      (node (ref "R16") (pin "2") (pinfunction "2_2") (pintype "passive"))
      (node (ref "TP9") (pin "1") (pinfunction "G9_1") (pintype "passive"))
      (node (ref "VT3") (pin "1") (pinfunction "G_1") (pintype "passive"))
    )
    (net (code "29") (name "Net-(D3-C)") (class "Default")
      (node (ref "D3") (pin "1") (pinfunction "C_1") (pintype "passive"))
      (node (ref "D4") (pin "1") (pinfunction "C_1") (pintype "passive"))
      (node (ref "R11") (pin "2") (pinfunction "2_2") (pintype "passive"))
      (node (ref "R13") (pin "2") (pinfunction "2_2") (pintype "passive"))
      (node (ref "TP11") (pin "1") (pinfunction "G9_1") (pintype "passive"))
      (node (ref "U4") (pin "6") (pinfunction "VO_6") (pintype "output"))
      (node (ref "U4") (pin "7") (pinfunction "VO_7") (pintype "output"))
      (node (ref "VD6") (pin "2") (pinfunction "A_2") (pintype "passive"))
    )
    (net (code "30") (name "Net-(D4-A)") (class "Default")
      (node (ref "D4") (pin "2") (pinfunction "A_2") (pintype "passive"))
      (node (ref "R13") (pin "1") (pinfunction "1_1") (pintype "passive"))
      (node (ref "R15") (pin "2") (pinfunction "2_2") (pintype "passive"))
      (node (ref "TP10") (pin "1") (pinfunction "G9_1") (pintype "passive"))
      (node (ref "VT4") (pin "1") (pinfunction "G_1") (pintype "passive"))
    )
    (net (code "31") (name "Net-(J1-17)") (class "Default")
      (node (ref "J1") (pin "1") (pinfunction "17_1") (pintype "passive"))
      (node (ref "R1") (pin "2") (pinfunction "2_2") (pintype "passive"))
      (node (ref "U1") (pin "5") (pinfunction "-IP_5") (pintype "passive"))
    )
    (net (code "32") (name "Net-(R1-Pad1)") (class "Default")
      (node (ref "R1") (pin "1") (pinfunction "1_1") (pintype "passive"))
      (node (ref "R7") (pin "2") (pinfunction "2_2") (pintype "passive"))
    )
    (net (code "33") (name "Net-(R2-Pad1)") (class "Default")
      (node (ref "R2") (pin "1") (pinfunction "1_1") (pintype "passive"))
      (node (ref "R8") (pin "2") (pinfunction "2_2") (pintype "passive"))
    )
    (net (code "34") (name "Net-(R7-Pad1)") (class "Default")
      (node (ref "R7") (pin "1") (pinfunction "1_1") (pintype "passive"))
      (node (ref "R9") (pin "2") (pinfunction "2_2") (pintype "passive"))
    )
    (net (code "35") (name "Net-(R10-Pad2)") (class "Default")
      (node (ref "R10") (pin "2") (pinfunction "2_2") (pintype "passive"))
      (node (ref "R8") (pin "1") (pinfunction "1_1") (pintype "passive"))
    )
    (net (code "36") (name "Net-(TP3-G9)") (class "Default")
      (node (ref "L1") (pin "2") (pinfunction "2_2") (pintype "passive"))
      (node (ref "TP3") (pin "1") (pinfunction "G9_1") (pintype "passive"))
      (node (ref "VD1") (pin "3") (pinfunction "3_3") (pintype "passive"))
      (node (ref "VD3") (pin "3") (pinfunction "3_3") (pintype "passive"))
      (node (ref "VT3") (pin "2") (pinfunction "C_2") (pintype "passive"))
      (node (ref "VT4") (pin "2") (pinfunction "C_2") (pintype "passive"))
    )
    (net (code "37") (name "Net-(TP14-G9)") (class "Default")
      (node (ref "C14") (pin "2") (pinfunction "2_2") (pintype "passive"))
      (node (ref "R10") (pin "1") (pinfunction "1_1") (pintype "passive"))
      (node (ref "R12") (pin "1") (pinfunction "1_1") (pintype "passive"))
      (node (ref "R19") (pin "2") (pinfunction "2_2") (pintype "passive"))
      (node (ref "TP14") (pin "1") (pinfunction "G9_1") (pintype "passive"))
    )
    (net (code "38") (name "Net-(TP15-G9)") (class "Default")
      (node (ref "C15") (pin "2") (pinfunction "2_2") (pintype "passive"))
      (node (ref "R14") (pin "1") (pinfunction "1_1") (pintype "passive"))
      (node (ref "R20") (pin "2") (pinfunction "2_2") (pintype "passive"))
      (node (ref "R9") (pin "1") (pinfunction "1_1") (pintype "passive"))
      (node (ref "TP15") (pin "1") (pinfunction "G9_1") (pintype "passive"))
    )
    (net (code "39") (name "Net-(U2--IP)") (class "Default")
      (node (ref "R2") (pin "2") (pinfunction "2_2") (pintype "passive"))
      (node (ref "U2") (pin "5") (pinfunction "-IP_5") (pintype "passive"))
      (node (ref "VT1") (pin "2") (pinfunction "C_2") (pintype "passive"))
      (node (ref "VT2") (pin "2") (pinfunction "C_2") (pintype "passive"))
    )
    (net (code "40") (name "Net-(U10-+Vo)") (class "Default")
      (node (ref "C31") (pin "2") (pinfunction "2_2") (pintype "passive"))
      (node (ref "C33") (pin "1") (pinfunction "1_1") (pintype "passive"))
      (node (ref "C41") (pin "2") (pinfunction "2_2") (pintype "passive"))
      (node (ref "U10") (pin "4") (pinfunction "+Vo_4") (pintype "power_in"))
      (node (ref "U11") (pin "1") (pinfunction "VDD1_1") (pintype "power_in"))
      (node (ref "U6") (pin "1") (pinfunction "VDD1_1") (pintype "power_in"))
    )
    (net (code "41") (name "unconnected-(U3-NC-Pad1)") (class "Default")
      (node (ref "U3") (pin "1") (pinfunction "NC_1") (pintype "passive"))
    )
    (net (code "42") (name "unconnected-(U3-NC-Pad4)") (class "Default")
      (node (ref "U3") (pin "4") (pinfunction "NC_4") (pintype "passive"))
    )
    (net (code "43") (name "unconnected-(U4-NC-Pad1)") (class "Default")
      (node (ref "U4") (pin "1") (pinfunction "NC_1") (pintype "passive"))
    )
    (net (code "44") (name "unconnected-(U4-NC-Pad4)") (class "Default")
      (node (ref "U4") (pin "4") (pinfunction "NC_4") (pintype "passive"))
    )
  )
)
